# Top.net
KiCad netlist of a schematic drawn in Altium Designer
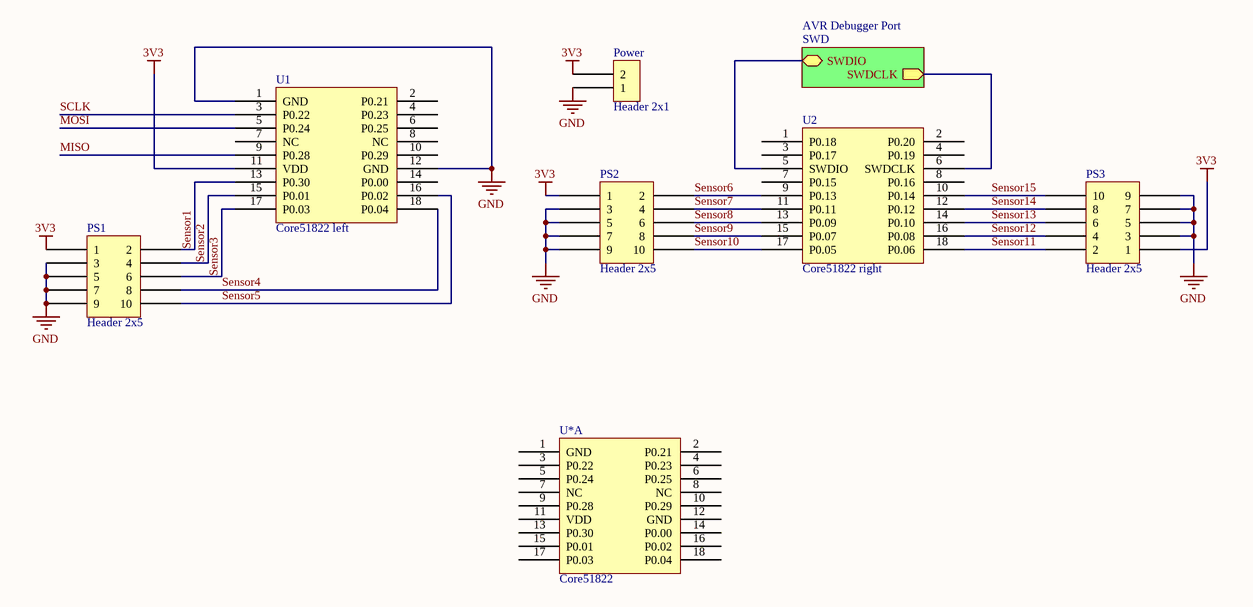
[diagram p0: Top.SchDoc]

(export (version "E")
  (design (tool "Eeschema 10.0.6"))
  (components
    (comp (ref "Power")
      (value "Header 2x1")
      (footprint "Screw terminal 2 pin RM 5mm")
      (libsource (lib "Headers") (part "Header 2x1"))
    )
    (comp (ref "PS1")
      (value "Header 2x5")
      (footprint "Header 2x5 IDC SMT")
      (libsource (lib "Headers") (part "Header 2x5"))
    )
    (comp (ref "PS2")
      (value "Header 2x5")
      (footprint "Header 2x5 IDC SMT")
      (libsource (lib "Headers") (part "Header 2x5"))
    )
    (comp (ref "PS3")
      (value "Header 2x5")
      (footprint "Header 2x5 IDC SMT")
      (libsource (lib "") (part "Header 2x5_1"))
    )
    (comp (ref "U*")
      (value "Core51822")
      (footprint "Core51822 Layout")
      (libsource (lib "Modules") (part "Core51822"))
    )
    (comp (ref "U1")
      (value "Core51822 left")
      (footprint "Header 2.00 2x9 SMD")
      (libsource (lib "Modules") (part "Core51822 left"))
    )
    (comp (ref "U2")
      (value "Core51822 right")
      (footprint "Header 2.00 2x9 SMD")
      (libsource (lib "Modules") (part "Core51822 right"))
    )
  )
  (nets
    (net (code "1") (name "/MISO") (class "Default")
      (node (ref "U1") (pin "9") (pinfunction "P0.28_9") (pintype "passive"))
    )
    (net (code "2") (name "/MOSI") (class "Default")
      (node (ref "U1") (pin "5") (pinfunction "P0.24_5") (pintype "passive"))
    )
    (net (code "3") (name "/SCLK") (class "Default")
      (node (ref "U1") (pin "3") (pinfunction "P0.22_3") (pintype "passive"))
    )
    (net (code "4") (name "/SWDCLK") (class "Default")
      (node (ref "U2") (pin "6") (pinfunction "SWDCLK_6") (pintype "passive"))
    )
    (net (code "5") (name "/SWDIO") (class "Default")
      (node (ref "U2") (pin "5") (pinfunction "SWDIO_5") (pintype "passive"))
    )
    (net (code "6") (name "/Sensor1") (class "Default")
      (node (ref "PS1") (pin "2") (pinfunction "2_2") (pintype "passive"))
      (node (ref "U1") (pin "13") (pinfunction "P0.30_13") (pintype "passive"))
    )
    (net (code "7") (name "/Sensor2") (class "Default")
      (node (ref "PS1") (pin "4") (pinfunction "4_4") (pintype "passive"))
      (node (ref "U1") (pin "15") (pinfunction "P0.01_15") (pintype "passive"))
    )
    (net (code "8") (name "/Sensor3") (class "Default")
      (node (ref "PS1") (pin "6") (pinfunction "6_6") (pintype "passive"))
      (node (ref "U1") (pin "17") (pinfunction "P0.03_17") (pintype "passive"))
    )
    (net (code "9") (name "/Sensor4") (class "Default")
      (node (ref "PS1") (pin "8") (pinfunction "8_8") (pintype "passive"))
      (node (ref "U1") (pin "18") (pinfunction "P0.04_18") (pintype "passive"))
    )
    (net (code "10") (name "/Sensor5") (class "Default")
      (node (ref "PS1") (pin "10") (pinfunction "10_10") (pintype "passive"))
      (node (ref "U1") (pin "16") (pinfunction "P0.02_16") (pintype "passive"))
    )
    (net (code "11") (name "/Sensor6") (class "Default")
      (node (ref "PS2") (pin "2") (pinfunction "2_2") (pintype "passive"))
      (node (ref "U2") (pin "9") (pinfunction "P0.13_9") (pintype "passive"))
    )
    (net (code "12") (name "/Sensor7") (class "Default")
      (node (ref "PS2") (pin "4") (pinfunction "4_4") (pintype "passive"))
      (node (ref "U2") (pin "11") (pinfunction "P0.11_11") (pintype "passive"))
    )
    (net (code "13") (name "/Sensor8") (class "Default")
      (node (ref "PS2") (pin "6") (pinfunction "6_6") (pintype "passive"))
      (node (ref "U2") (pin "13") (pinfunction "P0.09_13") (pintype "passive"))
    )
    (net (code "14") (name "/Sensor9") (class "Default")
      (node (ref "PS2") (pin "8") (pinfunction "8_8") (pintype "passive"))
      (node (ref "U2") (pin "15") (pinfunction "P0.07_15") (pintype "passive"))
    )
    (net (code "15") (name "/Sensor10") (class "Default")
      (node (ref "PS2") (pin "10") (pinfunction "10_10") (pintype "passive"))
      (node (ref "U2") (pin "17") (pinfunction "P0.05_17") (pintype "passive"))
    )
    (net (code "16") (name "/Sensor11") (class "Default")
      (node (ref "PS3") (pin "2") (pinfunction "2_2") (pintype "passive"))
      (node (ref "U2") (pin "18") (pinfunction "P0.06_18") (pintype "passive"))
    )
    (net (code "17") (name "/Sensor12") (class "Default")
      (node (ref "PS3") (pin "4") (pinfunction "4_4") (pintype "passive"))
      (node (ref "U2") (pin "16") (pinfunction "P0.08_16") (pintype "passive"))
    )
    (net (code "18") (name "/Sensor13") (class "Default")
      (node (ref "PS3") (pin "6") (pinfunction "6_6") (pintype "passive"))
      (node (ref "U2") (pin "14") (pinfunction "P0.10_14") (pintype "passive"))
    )
    (net (code "19") (name "/Sensor14") (class "Default")
      (node (ref "PS3") (pin "8") (pinfunction "8_8") (pintype "passive"))
      (node (ref "U2") (pin "12") (pinfunction "P0.12_12") (pintype "passive"))
    )
    (net (code "20") (name "/Sensor15") (class "Default")
      (node (ref "PS3") (pin "10") (pinfunction "10_10") (pintype "passive"))
      (node (ref "U2") (pin "10") (pinfunction "P0.14_10") (pintype "passive"))
    )
    (net (code "21") (name "3V3") (class "Default")
      (node (ref "PS1") (pin "1") (pinfunction "1_1") (pintype "passive"))
      (node (ref "PS2") (pin "1") (pinfunction "1_1") (pintype "passive"))
      (node (ref "PS3") (pin "1") (pinfunction "1_1") (pintype "passive"))
      (node (ref "Power") (pin "2") (pinfunction "2_2") (pintype "passive"))
      (node (ref "U1") (pin "11") (pinfunction "VDD_11") (pintype "passive"))
    )
    (net (code "22") (name "GND") (class "Default")
      (node (ref "PS1") (pin "3") (pinfunction "3_3") (pintype "passive"))
      (node (ref "PS1") (pin "5") (pinfunction "5_5") (pintype "passive"))
      (node (ref "PS1") (pin "7") (pinfunction "7_7") (pintype "passive"))
      (node (ref "PS1") (pin "9") (pinfunction "9_9") (pintype "passive"))
      (node (ref "PS2") (pin "3") (pinfunction "3_3") (pintype "passive"))
      (node (ref "PS2") (pin "5") (pinfunction "5_5") (pintype "passive"))
      (node (ref "PS2") (pin "7") (pinfunction "7_7") (pintype "passive"))
      (node (ref "PS2") (pin "9") (pinfunction "9_9") (pintype "passive"))
      (node (ref "PS3") (pin "3") (pinfunction "3_3") (pintype "passive"))
      (node (ref "PS3") (pin "5") (pinfunction "5_5") (pintype "passive"))
      (node (ref "PS3") (pin "7") (pinfunction "7_7") (pintype "passive"))
      (node (ref "PS3") (pin "9") (pinfunction "9_9") (pintype "passive"))
      (node (ref "Power") (pin "1") (pinfunction "1_1") (pintype "passive"))
      (node (ref "U1") (pin "1") (pinfunction "GND_1") (pintype "passive"))
      (node (ref "U1") (pin "12") (pinfunction "GND_12") (pintype "passive"))
    )
    (net (code "23") (name "unconnected-(U*A-GND-Pad1)") (class "Default")
      (node (ref "U*") (pin "1") (pinfunction "GND_1") (pintype "passive"))
    )
    (net (code "24") (name "unconnected-(U*A-GND-Pad12)") (class "Default")
      (node (ref "U*") (pin "12") (pinfunction "GND_12") (pintype "passive"))
    )
    (net (code "25") (name "unconnected-(U*A-NC-Pad7)") (class "Default")
      (node (ref "U*") (pin "7") (pinfunction "NC_7") (pintype "passive"))
    )
    (net (code "26") (name "unconnected-(U*A-NC-Pad8)") (class "Default")
      (node (ref "U*") (pin "8") (pinfunction "NC_8") (pintype "passive"))
    )
    (net (code "27") (name "unconnected-(U*A-P0.00-Pad14)") (class "Default")
      (node (ref "U*") (pin "14") (pinfunction "P0.00_14") (pintype "passive"))
    )
    (net (code "28") (name "unconnected-(U*A-P0.01-Pad15)") (class "Default")
      (node (ref "U*") (pin "15") (pinfunction "P0.01_15") (pintype "passive"))
    )
    (net (code "29") (name "unconnected-(U*A-P0.02-Pad16)") (class "Default")
      (node (ref "U*") (pin "16") (pinfunction "P0.02_16") (pintype "passive"))
    )
    (net (code "30") (name "unconnected-(U*A-P0.03-Pad17)") (class "Default")
      (node (ref "U*") (pin "17") (pinfunction "P0.03_17") (pintype "passive"))
    )
    (net (code "31") (name "unconnected-(U*A-P0.04-Pad18)") (class "Default")
      (node (ref "U*") (pin "18") (pinfunction "P0.04_18") (pintype "passive"))
    )
    (net (code "32") (name "unconnected-(U*A-P0.21-Pad2)") (class "Default")
      (node (ref "U*") (pin "2") (pinfunction "P0.21_2") (pintype "passive"))
    )
    (net (code "33") (name "unconnected-(U*A-P0.22-Pad3)") (class "Default")
      (node (ref "U*") (pin "3") (pinfunction "P0.22_3") (pintype "passive"))
    )
    (net (code "34") (name "unconnected-(U*A-P0.23-Pad4)") (class "Default")
      (node (ref "U*") (pin "4") (pinfunction "P0.23_4") (pintype "passive"))
    )
    (net (code "35") (name "unconnected-(U*A-P0.24-Pad5)") (class "Default")
      (node (ref "U*") (pin "5") (pinfunction "P0.24_5") (pintype "passive"))
    )
    (net (code "36") (name "unconnected-(U*A-P0.25-Pad6)") (class "Default")
      (node (ref "U*") (pin "6") (pinfunction "P0.25_6") (pintype "passive"))
    )
    (net (code "37") (name "unconnected-(U*A-P0.28-Pad9)") (class "Default")
      (node (ref "U*") (pin "9") (pinfunction "P0.28_9") (pintype "passive"))
    )
    (net (code "38") (name "unconnected-(U*A-P0.29-Pad10)") (class "Default")
      (node (ref "U*") (pin "10") (pinfunction "P0.29_10") (pintype "passive"))
    )
    (net (code "39") (name "unconnected-(U*A-P0.30-Pad13)") (class "Default")
      (node (ref "U*") (pin "13") (pinfunction "P0.30_13") (pintype "passive"))
    )
    (net (code "40") (name "unconnected-(U*A-VDD-Pad11)") (class "Default")
      (node (ref "U*") (pin "11") (pinfunction "VDD_11") (pintype "passive"))
    )
    (net (code "41") (name "unconnected-(U1-NC-Pad7)") (class "Default")
      (node (ref "U1") (pin "7") (pinfunction "NC_7") (pintype "passive"))
    )
    (net (code "42") (name "unconnected-(U1-NC-Pad8)") (class "Default")
      (node (ref "U1") (pin "8") (pinfunction "NC_8") (pintype "passive"))
    )
    (net (code "43") (name "unconnected-(U1-P0.00-Pad14)") (class "Default")
      (node (ref "U1") (pin "14") (pinfunction "P0.00_14") (pintype "passive"))
    )
    (net (code "44") (name "unconnected-(U1-P0.21-Pad2)") (class "Default")
      (node (ref "U1") (pin "2") (pinfunction "P0.21_2") (pintype "passive"))
    )
    (net (code "45") (name "unconnected-(U1-P0.23-Pad4)") (class "Default")
      (node (ref "U1") (pin "4") (pinfunction "P0.23_4") (pintype "passive"))
    )
    (net (code "46") (name "unconnected-(U1-P0.25-Pad6)") (class "Default")
      (node (ref "U1") (pin "6") (pinfunction "P0.25_6") (pintype "passive"))
    )
    (net (code "47") (name "unconnected-(U1-P0.29-Pad10)") (class "Default")
      (node (ref "U1") (pin "10") (pinfunction "P0.29_10") (pintype "passive"))
    )
    (net (code "48") (name "unconnected-(U2-P0.15-Pad7)") (class "Default")
      (node (ref "U2") (pin "7") (pinfunction "P0.15_7") (pintype "passive"))
    )
    (net (code "49") (name "unconnected-(U2-P0.16-Pad8)") (class "Default")
      (node (ref "U2") (pin "8") (pinfunction "P0.16_8") (pintype "passive"))
    )
    (net (code "50") (name "unconnected-(U2-P0.17-Pad3)") (class "Default")
      (node (ref "U2") (pin "3") (pinfunction "P0.17_3") (pintype "power_in"))
    )
    (net (code "51") (name "unconnected-(U2-P0.18-Pad1)") (class "Default")
      (node (ref "U2") (pin "1") (pinfunction "P0.18_1") (pintype "passive"))
    )
    (net (code "52") (name "unconnected-(U2-P0.19-Pad4)") (class "Default")
      (node (ref "U2") (pin "4") (pinfunction "P0.19_4") (pintype "passive"))
    )
    (net (code "53") (name "unconnected-(U2-P0.20-Pad2)") (class "Default")
      (node (ref "U2") (pin "2") (pinfunction "P0.20_2") (pintype "passive"))
    )
  )
)
